# USB.net
KiCad netlist of a schematic drawn in Altium Designer
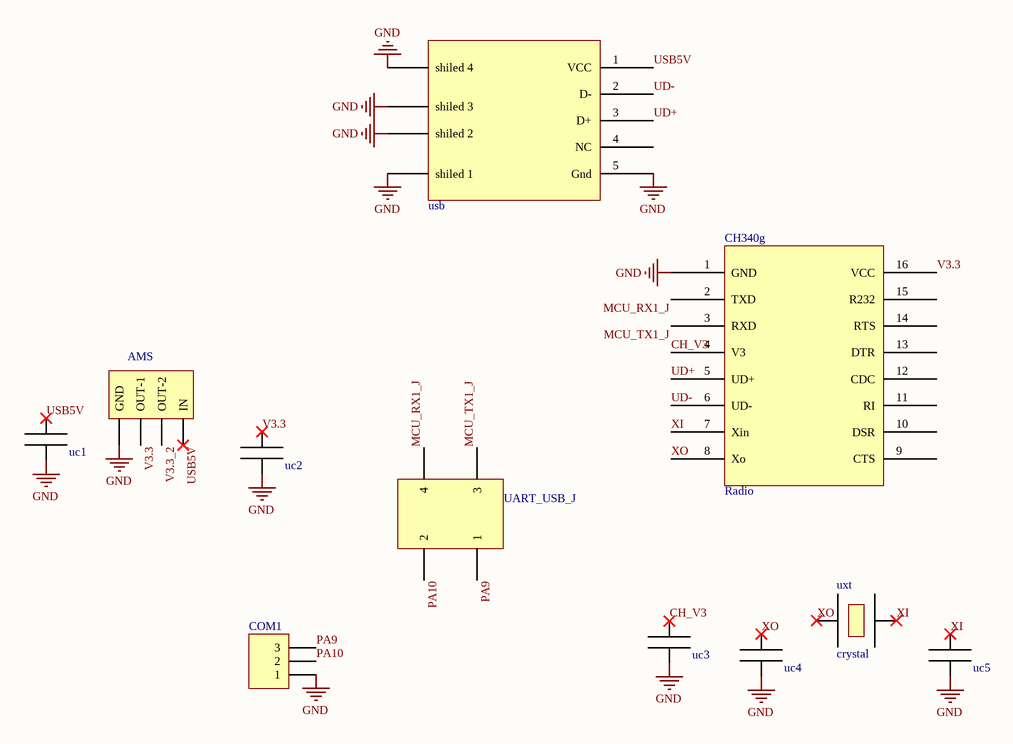
[diagram p0: USB.SchDoc]

(export (version "E")
  (design (tool "Eeschema 10.0.6"))
  (components
    (comp (ref "AMS")
      (value "Regulator")
      (footprint "abr_fp_SOT-223_3d")
      (libsource (lib "abr_reg_smd-96-04") (part "abr_reg_AMS1117"))
    )
    (comp (ref "CH340g")
      (value "Radio")
      (footprint "abr_usb_ch344g_3d")
      (libsource (lib "lible") (part "abr_usb_ch340g"))
    )
    (comp (ref "COM1")
      (value "Header 3")
      (footprint "HDR1X3")
      (description "Header, 3-Pin")
      (fields (field (name "PUBLISHER") "Altium Limited"))
      (libsource (lib "Miscellaneous Connectors") (part "Header 3"))
    )
    (comp (ref "UART_USB_J")
      (value "pin header 2mm")
      (footprint "abr_ph_2x2_2mm_3d_male")
      (libsource (lib "abr_ph_2mm_96_02") (part "abr_2x2_2mm"))
    )
    (comp (ref "uc1")
      (value "1uf")
      (footprint "abr_cap_0805_3d")
      (libsource (lib "abr_smd_0805_all") (part "abr_cap_0805"))
    )
    (comp (ref "uc2")
      (value "1uf")
      (footprint "abr_cap_0805_3d")
      (libsource (lib "abr_smd_0805_all") (part "abr_cap_0805"))
    )
    (comp (ref "uc3")
      (value "100nf")
      (footprint "abr_cap_0805_3d")
      (libsource (lib "abr_smd_0805_all") (part "abr_cap_0805"))
    )
    (comp (ref "uc4")
      (value "22pf")
      (footprint "abr_cap_0805_3d")
      (libsource (lib "abr_smd_0805_all") (part "abr_cap_0805"))
    )
    (comp (ref "uc5")
      (value "22pf")
      (footprint "abr_cap_0805_3d")
      (libsource (lib "abr_smd_0805_all") (part "abr_cap_0805"))
    )
    (comp (ref "usb")
      (value "usb connector")
      (footprint "abr_usb_micro_hoawey_p6_3d")
      (libsource (lib "usb_related_96_02") (part "abr_usb_micro_female"))
    )
    (comp (ref "uxt")
      (value "crystal")
      (footprint "abr_crystal_dip_3d")
      (libsource (lib "abr_crystal_osc_96_02") (part "abr_crystal"))
    )
  )
  (nets
    (net (code "1") (name "/CH_V3") (class "Default")
      (node (ref "CH340g") (pin "4") (pinfunction "V3_4") (pintype "passive"))
      (node (ref "uc3") (pin "1") (pinfunction "10_1") (pintype "passive"))
    )
    (net (code "2") (name "/MCU_RX1_J") (class "Default")
      (node (ref "CH340g") (pin "2") (pinfunction "TXD_2") (pintype "passive"))
      (node (ref "UART_USB_J") (pin "4") (pinfunction "4_4") (pintype "passive"))
    )
    (net (code "3") (name "/MCU_TX1_J") (class "Default")
      (node (ref "CH340g") (pin "3") (pinfunction "RXD_3") (pintype "passive"))
      (node (ref "UART_USB_J") (pin "3") (pinfunction "3_3") (pintype "passive"))
    )
    (net (code "4") (name "/PA9") (class "Default")
      (node (ref "COM1") (pin "3") (pinfunction "3_3") (pintype "passive"))
      (node (ref "UART_USB_J") (pin "1") (pinfunction "1_1") (pintype "passive"))
    )
    (net (code "5") (name "/PA10") (class "Default")
      (node (ref "COM1") (pin "2") (pinfunction "2_2") (pintype "passive"))
      (node (ref "UART_USB_J") (pin "2") (pinfunction "2_2") (pintype "passive"))
    )
    (net (code "6") (name "/UD+") (class "Default")
      (node (ref "CH340g") (pin "5") (pinfunction "UD+_5") (pintype "passive"))
      (node (ref "usb") (pin "3") (pinfunction "D+_3") (pintype "passive"))
    )
    (net (code "7") (name "/UD-") (class "Default")
      (node (ref "CH340g") (pin "6") (pinfunction "UD-_6") (pintype "passive"))
      (node (ref "usb") (pin "2") (pinfunction "D-_2") (pintype "passive"))
    )
    (net (code "8") (name "/USB5V") (class "Default")
      (node (ref "AMS") (pin "3") (pinfunction "IN_3") (pintype "passive"))
      (node (ref "uc1") (pin "1") (pinfunction "10_1") (pintype "passive"))
      (node (ref "usb") (pin "1") (pinfunction "VCC_1") (pintype "passive"))
    )
    (net (code "9") (name "/V3.3") (class "Default")
      (node (ref "AMS") (pin "2") (pinfunction "OUT-1_2") (pintype "passive"))
      (node (ref "CH340g") (pin "16") (pinfunction "VCC_16") (pintype "passive"))
      (node (ref "uc2") (pin "1") (pinfunction "10_1") (pintype "passive"))
    )
    (net (code "10") (name "/V3.3_2") (class "Default")
      (node (ref "AMS") (pin "4") (pinfunction "OUT-2_4") (pintype "passive"))
    )
    (net (code "11") (name "/XI") (class "Default")
      (node (ref "CH340g") (pin "7") (pinfunction "Xin_7") (pintype "passive"))
      (node (ref "uc5") (pin "1") (pinfunction "10_1") (pintype "passive"))
      (node (ref "uxt") (pin "2") (pintype "passive"))
    )
    (net (code "12") (name "/XO") (class "Default")
      (node (ref "CH340g") (pin "8") (pinfunction "Xo_8") (pintype "passive"))
      (node (ref "uc4") (pin "1") (pinfunction "10_1") (pintype "passive"))
      (node (ref "uxt") (pin "1") (pintype "passive"))
    )
    (net (code "13") (name "GND") (class "Default")
      (node (ref "AMS") (pin "1") (pinfunction "GND_1") (pintype "passive"))
      (node (ref "CH340g") (pin "1") (pinfunction "GND_1") (pintype "passive"))
      (node (ref "COM1") (pin "1") (pinfunction "1_1") (pintype "passive"))
      (node (ref "uc1") (pin "0") (pinfunction "2_0") (pintype "passive"))
      (node (ref "uc2") (pin "0") (pinfunction "2_0") (pintype "passive"))
      (node (ref "uc3") (pin "0") (pinfunction "2_0") (pintype "passive"))
      (node (ref "uc4") (pin "0") (pinfunction "2_0") (pintype "passive"))
      (node (ref "uc5") (pin "0") (pinfunction "2_0") (pintype "passive"))
      (node (ref "usb") (pin "5") (pinfunction "Gnd_5") (pintype "passive"))
      (node (ref "usb") (pin "6") (pinfunction "shiled_1_6") (pintype "passive"))
      (node (ref "usb") (pin "7") (pinfunction "shiled_2_7") (pintype "passive"))
      (node (ref "usb") (pin "8") (pinfunction "shiled_3_8") (pintype "passive"))
      (node (ref "usb") (pin "9") (pinfunction "shiled_4_9") (pintype "passive"))
    )
    (net (code "14") (name "unconnected-(CH340g-CDC-Pad12)") (class "Default")
      (node (ref "CH340g") (pin "12") (pinfunction "CDC_12") (pintype "passive"))
    )
    (net (code "15") (name "unconnected-(CH340g-CTS-Pad9)") (class "Default")
      (node (ref "CH340g") (pin "9") (pinfunction "CTS_9") (pintype "passive"))
    )
    (net (code "16") (name "unconnected-(CH340g-DSR-Pad10)") (class "Default")
      (node (ref "CH340g") (pin "10") (pinfunction "DSR_10") (pintype "passive"))
    )
    (net (code "17") (name "unconnected-(CH340g-DTR-Pad13)") (class "Default")
      (node (ref "CH340g") (pin "13") (pinfunction "DTR_13") (pintype "passive"))
    )
    (net (code "18") (name "unconnected-(CH340g-R232-Pad15)") (class "Default")
      (node (ref "CH340g") (pin "15") (pinfunction "R232_15") (pintype "passive"))
    )
    (net (code "19") (name "unconnected-(CH340g-RI-Pad11)") (class "Default")
      (node (ref "CH340g") (pin "11") (pinfunction "RI_11") (pintype "passive"))
    )
    (net (code "20") (name "unconnected-(CH340g-RTS-Pad14)") (class "Default")
      (node (ref "CH340g") (pin "14") (pinfunction "RTS_14") (pintype "passive"))
    )
    (net (code "21") (name "unconnected-(usb-NC-Pad4)") (class "Default")
      (node (ref "usb") (pin "4") (pinfunction "NC_4") (pintype "passive"))
    )
  )
)
